# dooraccessystem.net
KiCad netlist of a schematic drawn in EAGLE
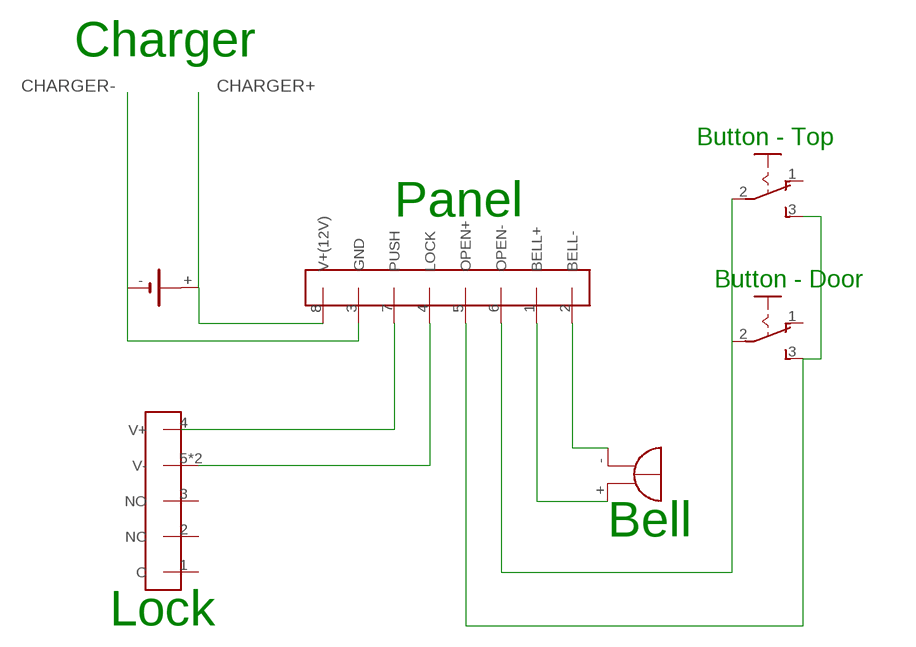
[diagram p0: schematic, sheet 1]

(export (version "E")
  (design (tool "Eeschema 10.0.6"))
  (components
    (comp (ref "BATTERY")
      (value "CRAA")
      (footprint "eagle-import:CRAA")
      (libsource (lib "eagle-import") (part "CRAA"))
    )
    (comp (ref "LOCK")
      (value "MAGNETLOCK")
      (footprint "eagle-import:DIL06")
      (libsource (lib "eagle-import") (part "MAGNETLOCK"))
    )
    (comp (ref "PANEL")
      (value "DOORACCESSFRONTPANEL")
      (footprint "eagle-import:DIL08")
      (libsource (lib "eagle-import") (part "DOORACCESSFRONTPANEL"))
    )
    (comp (ref "S1")
      (value "255SB")
      (footprint "eagle-import:255SB")
      (libsource (lib "eagle-import") (part "255SB"))
    )
    (comp (ref "S2")
      (value "255SB")
      (footprint "eagle-import:255SB")
      (libsource (lib "eagle-import") (part "255SB"))
    )
    (comp (ref "SPEAKER")
      (value "EB2209A")
      (footprint "eagle-import:EB2209A")
      (libsource (lib "eagle-import") (part "EB2209A"))
    )
  )
  (nets
    (net (code "1") (name "/CHARGER+") (class "Default")
      (node (ref "BATTERY") (pin "+") (pinfunction "+_+") (pintype "passive"))
      (node (ref "PANEL") (pin "8") (pinfunction "V+(12V)_8") (pintype "bidirectional"))
    )
    (net (code "2") (name "/CHARGER-") (class "Default")
      (node (ref "BATTERY") (pin "-") (pinfunction "-_-") (pintype "passive"))
      (node (ref "PANEL") (pin "3") (pinfunction "GND_3") (pintype "bidirectional"))
    )
    (net (code "3") (name "/V+") (class "Default")
      (node (ref "LOCK") (pin "4") (pinfunction "V+_4") (pintype "power_in"))
    )
    (net (code "4") (name "Net-(PANEL-BELL+)") (class "Default")
      (node (ref "PANEL") (pin "1") (pinfunction "BELL+_1") (pintype "bidirectional"))
      (node (ref "SPEAKER") (pin "+") (pinfunction "+_+") (pintype "passive"))
    )
    (net (code "5") (name "Net-(PANEL-BELL-)") (class "Default")
      (node (ref "PANEL") (pin "2") (pinfunction "BELL-_2") (pintype "bidirectional"))
      (node (ref "SPEAKER") (pin "-") (pinfunction "-_-") (pintype "passive"))
    )
    (net (code "6") (name "Net-(PANEL-LOCK)") (class "Default")
      (node (ref "LOCK") (pin "5") (pinfunction "V-_5") (pintype "power_in"))
      (node (ref "LOCK") (pin "6") (pinfunction "V-_6") (pintype "power_in"))
      (node (ref "PANEL") (pin "4") (pinfunction "LOCK_4") (pintype "bidirectional"))
    )
    (net (code "7") (name "Net-(PANEL-OPEN+)") (class "Default")
      (node (ref "PANEL") (pin "5") (pinfunction "OPEN+_5") (pintype "bidirectional"))
      (node (ref "S1") (pin "3") (pinfunction "S_3") (pintype "passive"))
      (node (ref "S2") (pin "3") (pinfunction "S_3") (pintype "passive"))
    )
    (net (code "8") (name "Net-(PANEL-OPEN-)") (class "Default")
      (node (ref "PANEL") (pin "6") (pinfunction "OPEN-_6") (pintype "bidirectional"))
      (node (ref "S1") (pin "2") (pinfunction "P_2") (pintype "passive"))
      (node (ref "S2") (pin "2") (pinfunction "P_2") (pintype "passive"))
    )
    (net (code "9") (name "unconnected-(BATTERY-+-Pad+@1)") (class "Default")
      (node (ref "BATTERY") (pin "+@1") (pinfunction "+_+@1") (pintype "passive"))
    )
    (net (code "10") (name "unconnected-(LOCK-C-Pad1)") (class "Default")
      (node (ref "LOCK") (pin "1") (pinfunction "C_1") (pintype "output"))
    )
    (net (code "11") (name "unconnected-(LOCK-NC-Pad2)") (class "Default")
      (node (ref "LOCK") (pin "2") (pinfunction "NC_2") (pintype "output"))
    )
    (net (code "12") (name "unconnected-(LOCK-NO-Pad3)") (class "Default")
      (node (ref "LOCK") (pin "3") (pinfunction "NO_3") (pintype "output"))
    )
    (net (code "13") (name "unconnected-(PANEL-PUSH-Pad7)") (class "Default")
      (node (ref "PANEL") (pin "7") (pinfunction "PUSH_7") (pintype "bidirectional"))
    )
    (net (code "14") (name "unconnected-(S1-O-Pad1)") (class "Default")
      (node (ref "S1") (pin "1") (pinfunction "O_1") (pintype "passive"))
    )
    (net (code "15") (name "unconnected-(S2-O-Pad1)") (class "Default")
      (node (ref "S2") (pin "1") (pinfunction "O_1") (pintype "passive"))
    )
  )
)
